# Alim.net
KiCad netlist of a schematic drawn in Altium Designer
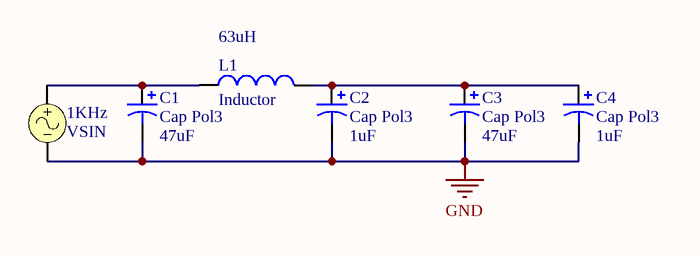
[diagram p0: Alim.SchDoc]

(export (version "E")
  (design (tool "Eeschema 10.0.6"))
  (components
    (comp (ref "1KHz")
      (value "VSIN")
      (description "Sinusoidal Voltage Source")
      (fields (field (name "PUBLISHER") "Altium Limited"))
      (libsource (lib "Simulation Sources") (part "VSIN"))
    )
    (comp (ref "C1")
      (value "Cap Pol3")
      (footprint "CAPC4564L")
      (description "Polarized Capacitor (Surface Mount)")
      (fields (field (name "ALTIUM_VALUE") "47uF") (field (name "PUBLISHER") "Altium Limited"))
      (libsource (lib "Miscellaneous Devices") (part "Cap Pol3"))
    )
    (comp (ref "C2")
      (value "Cap Pol3")
      (footprint "CAPC4564L")
      (description "Polarized Capacitor (Surface Mount)")
      (fields (field (name "ALTIUM_VALUE") "1uF") (field (name "PUBLISHER") "Altium Limited"))
      (libsource (lib "Miscellaneous Devices") (part "Cap Pol3"))
    )
    (comp (ref "C3")
      (value "Cap Pol3")
      (footprint "CAPC4564L")
      (description "Polarized Capacitor (Surface Mount)")
      (fields (field (name "ALTIUM_VALUE") "47uF") (field (name "PUBLISHER") "Altium Limited"))
      (libsource (lib "Miscellaneous Devices") (part "Cap Pol3"))
    )
    (comp (ref "C4")
      (value "Cap Pol3")
      (footprint "CAPC4564L")
      (description "Polarized Capacitor (Surface Mount)")
      (fields (field (name "ALTIUM_VALUE") "1uF") (field (name "PUBLISHER") "Altium Limited"))
      (libsource (lib "Miscellaneous Devices") (part "Cap Pol3"))
    )
    (comp (ref "L1")
      (value "Inductor")
      (footprint "INDC3216AL")
      (fields (field (name "ALTIUM_VALUE") "63uH") (field (name "PUBLISHER") "Altium Limited"))
      (libsource (lib "Miscellaneous Devices") (part "Inductor"))
    )
  )
  (nets
    (net (code "1") (name "GND") (class "Default")
      (node (ref "1KHz") (pin "2") (pinfunction "2_2") (pintype "passive"))
      (node (ref "C1") (pin "2") (pinfunction "2_2") (pintype "passive"))
      (node (ref "C2") (pin "2") (pinfunction "2_2") (pintype "passive"))
      (node (ref "C3") (pin "2") (pinfunction "2_2") (pintype "passive"))
      (node (ref "C4") (pin "2") (pinfunction "2_2") (pintype "passive"))
    )
    (net (code "2") (name "Net-(1KHz-Pad1)") (class "Default")
      (node (ref "1KHz") (pin "1") (pinfunction "1_1") (pintype "passive"))
      (node (ref "C1") (pin "1") (pinfunction "1_1") (pintype "passive"))
      (node (ref "L1") (pin "1") (pinfunction "1_1") (pintype "passive"))
    )
    (net (code "3") (name "Net-(C2-Pad1)") (class "Default")
      (node (ref "C2") (pin "1") (pinfunction "1_1") (pintype "passive"))
      (node (ref "C3") (pin "1") (pinfunction "1_1") (pintype "passive"))
      (node (ref "C4") (pin "1") (pinfunction "1_1") (pintype "passive"))
      (node (ref "L1") (pin "2") (pinfunction "2_2") (pintype "passive"))
    )
  )
)
